# Power_-_3V3.net
KiCad netlist of a schematic drawn in Altium Designer
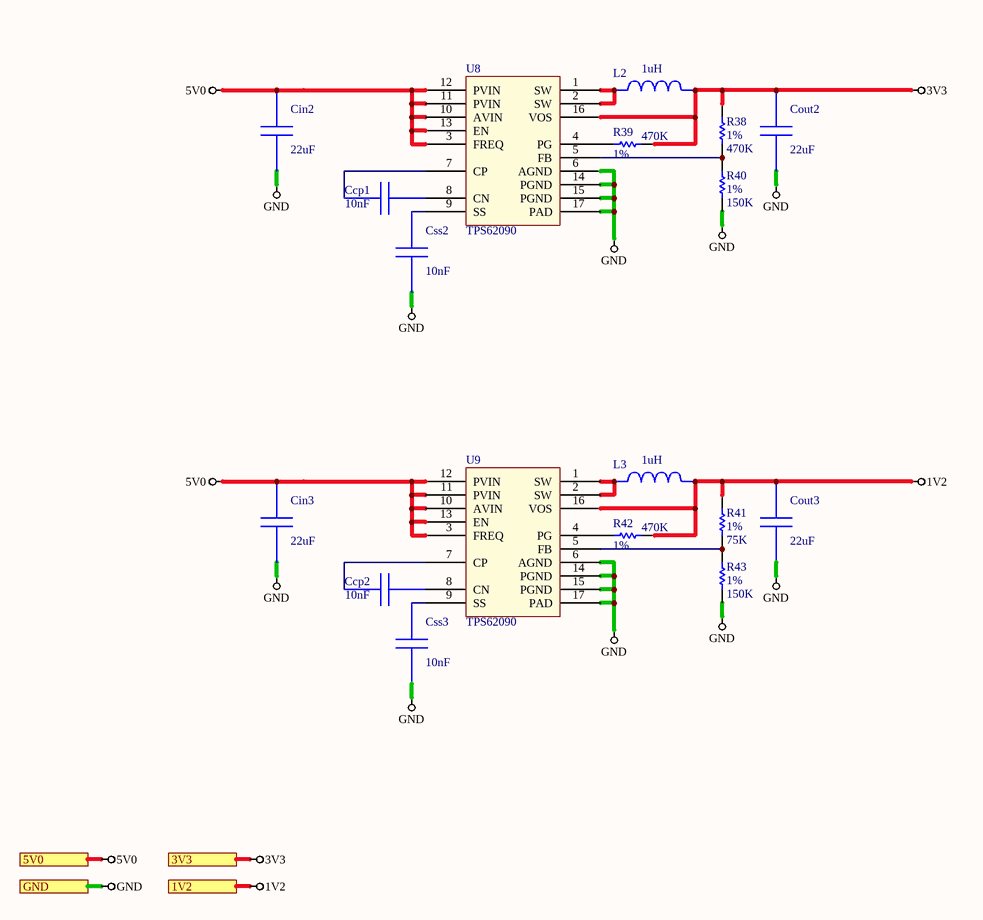
[diagram p0: Power - 3V3.SchDoc]

(export (version "E")
  (design (tool "Eeschema 10.0.6"))
  (components
    (comp (ref "Ccp1")
      (value "10nF")
      (footprint "CAPC0402(1005)60_L")
      (description "GRM155R71E103KA0")
      (fields (field (name "MANUFACTURER PART NUMBER") "GRM155R71E103KA01D"))
      (libsource (lib "TI WEBENCH") (part "Ccp"))
    )
    (comp (ref "Ccp2")
      (value "10nF")
      (footprint "CAPC0402(1005)60_L")
      (description "GRM155R71E103KA0")
      (fields (field (name "MANUFACTURER PART NUMBER") "GRM155R71E103KA01D"))
      (libsource (lib "TI WEBENCH") (part "Ccp"))
    )
    (comp (ref "Cin2")
      (value "22uF")
      (footprint "C-0805")
      (description "GRM21BR60J226ME3")
      (fields (field (name "MANUFACTURER PART NUMBER") "GRM21BR60J226ME39L"))
      (libsource (lib "TI WEBENCH") (part "Cout"))
    )
    (comp (ref "Cin3")
      (value "22uF")
      (footprint "C-0805")
      (description "GRM21BR60J226ME3")
      (fields (field (name "MANUFACTURER PART NUMBER") "GRM21BR60J226ME39L"))
      (libsource (lib "TI WEBENCH") (part "Cout"))
    )
    (comp (ref "Cout2")
      (value "22uF")
      (footprint "C-0805")
      (description "GRM21BR60J226ME3")
      (fields (field (name "MANUFACTURER PART NUMBER") "GRM21BR60J226ME39L"))
      (libsource (lib "TI WEBENCH") (part "Cout"))
    )
    (comp (ref "Cout3")
      (value "22uF")
      (footprint "C-0805")
      (description "GRM21BR60J226ME3")
      (fields (field (name "MANUFACTURER PART NUMBER") "GRM21BR60J226ME39L"))
      (libsource (lib "TI WEBENCH") (part "Cout"))
    )
    (comp (ref "Css2")
      (value "10nF")
      (footprint "CAPC0402(1005)60_L")
      (description "GRM155R71E103KA0")
      (fields (field (name "MANUFACTURER PART NUMBER") "GRM155R71E103KA01D"))
      (libsource (lib "TI WEBENCH") (part "Ccp"))
    )
    (comp (ref "Css3")
      (value "10nF")
      (footprint "CAPC0402(1005)60_L")
      (description "GRM155R71E103KA0")
      (fields (field (name "MANUFACTURER PART NUMBER") "GRM155R71E103KA01D"))
      (libsource (lib "TI WEBENCH") (part "Ccp"))
    )
    (comp (ref "L2")
      (value "1uH")
      (footprint "XFL4020")
      (fields (field (name "MANUFACTURER PART NUMBER") "XFL4020-102MEB"))
      (libsource (lib "FPGA-pcie") (part "Inductor-XFL4020-102MEB"))
    )
    (comp (ref "L3")
      (value "1uH")
      (footprint "XFL4020")
      (fields (field (name "MANUFACTURER PART NUMBER") "XFL4020-102MEB"))
      (libsource (lib "FPGA-pcie") (part "Inductor-XFL4020-102MEB"))
    )
    (comp (ref "R38")
      (value "1%")
      (footprint "RESC0402(1005)40_L")
      (description "Resistor")
      (fields (field (name "ALTIUM_VALUE") "470K") (field (name "PUBLISHER") "Altium Limited"))
      (libsource (lib "Miscellaneous Devices") (part "Res1"))
    )
    (comp (ref "R39")
      (value "1%")
      (footprint "RESC0402(1005)40_L")
      (description "Resistor")
      (fields (field (name "ALTIUM_VALUE") "470K") (field (name "PUBLISHER") "Altium Limited"))
      (libsource (lib "Miscellaneous Devices") (part "Res1"))
    )
    (comp (ref "R40")
      (value "1%")
      (footprint "RESC0402(1005)40_L")
      (description "Resistor")
      (fields (field (name "ALTIUM_VALUE") "150K") (field (name "PUBLISHER") "Altium Limited"))
      (libsource (lib "Miscellaneous Devices") (part "Res1"))
    )
    (comp (ref "R41")
      (value "1%")
      (footprint "RESC0402(1005)40_L")
      (description "Resistor")
      (fields (field (name "ALTIUM_VALUE") "75K") (field (name "PUBLISHER") "Altium Limited"))
      (libsource (lib "Miscellaneous Devices") (part "Res1"))
    )
    (comp (ref "R42")
      (value "1%")
      (footprint "RESC0402(1005)40_L")
      (description "Resistor")
      (fields (field (name "ALTIUM_VALUE") "470K") (field (name "PUBLISHER") "Altium Limited"))
      (libsource (lib "Miscellaneous Devices") (part "Res1"))
    )
    (comp (ref "R43")
      (value "1%")
      (footprint "RESC0402(1005)40_L")
      (description "Resistor")
      (fields (field (name "ALTIUM_VALUE") "150K") (field (name "PUBLISHER") "Altium Limited"))
      (libsource (lib "Miscellaneous Devices") (part "Res1"))
    )
    (comp (ref "U8")
      (value "TPS62090")
      (footprint "RGT16_1P7X1P7")
      (libsource (lib "Power") (part "TPS6209X"))
    )
    (comp (ref "U9")
      (value "TPS62090")
      (footprint "RGT16_1P7X1P7")
      (libsource (lib "Power") (part "TPS6209X"))
    )
  )
  (nets
    (net (code "1") (name "1V2") (class "Default")
      (node (ref "Cout3") (pin "1") (pinfunction "1_1") (pintype "passive"))
      (node (ref "L3") (pin "2") (pinfunction "2_2") (pintype "passive"))
      (node (ref "R41") (pin "2") (pinfunction "2_2") (pintype "passive"))
      (node (ref "R42") (pin "1") (pinfunction "1_1") (pintype "passive"))
      (node (ref "U9") (pin "16") (pinfunction "VOS_16") (pintype "passive"))
    )
    (net (code "2") (name "3V3") (class "Default")
      (node (ref "Cout2") (pin "1") (pinfunction "1_1") (pintype "passive"))
      (node (ref "L2") (pin "2") (pinfunction "2_2") (pintype "passive"))
      (node (ref "R38") (pin "2") (pinfunction "2_2") (pintype "passive"))
      (node (ref "R39") (pin "1") (pinfunction "1_1") (pintype "passive"))
      (node (ref "U8") (pin "16") (pinfunction "VOS_16") (pintype "passive"))
    )
    (net (code "3") (name "5V0") (class "Default")
      (node (ref "Cin2") (pin "1") (pinfunction "1_1") (pintype "passive"))
      (node (ref "Cin3") (pin "1") (pinfunction "1_1") (pintype "passive"))
      (node (ref "U8") (pin "10") (pinfunction "AVIN_10") (pintype "passive"))
      (node (ref "U8") (pin "11") (pinfunction "PVIN_11") (pintype "passive"))
      (node (ref "U8") (pin "12") (pinfunction "PVIN_12") (pintype "passive"))
      (node (ref "U8") (pin "13") (pinfunction "EN_13") (pintype "passive"))
      (node (ref "U8") (pin "3") (pinfunction "FREQ_3") (pintype "passive"))
      (node (ref "U9") (pin "10") (pinfunction "AVIN_10") (pintype "passive"))
      (node (ref "U9") (pin "11") (pinfunction "PVIN_11") (pintype "passive"))
      (node (ref "U9") (pin "12") (pinfunction "PVIN_12") (pintype "passive"))
      (node (ref "U9") (pin "13") (pinfunction "EN_13") (pintype "passive"))
      (node (ref "U9") (pin "3") (pinfunction "FREQ_3") (pintype "passive"))
    )
    (net (code "4") (name "GND") (class "Default")
      (node (ref "Cin2") (pin "2") (pinfunction "2_2") (pintype "passive"))
      (node (ref "Cin3") (pin "2") (pinfunction "2_2") (pintype "passive"))
      (node (ref "Cout2") (pin "2") (pinfunction "2_2") (pintype "passive"))
      (node (ref "Cout3") (pin "2") (pinfunction "2_2") (pintype "passive"))
      (node (ref "Css2") (pin "2") (pinfunction "2_2") (pintype "passive"))
      (node (ref "Css3") (pin "2") (pinfunction "2_2") (pintype "passive"))
      (node (ref "R40") (pin "1") (pinfunction "1_1") (pintype "passive"))
      (node (ref "R43") (pin "1") (pinfunction "1_1") (pintype "passive"))
      (node (ref "U8") (pin "14") (pinfunction "PGND_14") (pintype "passive"))
      (node (ref "U8") (pin "15") (pinfunction "PGND_15") (pintype "passive"))
      (node (ref "U8") (pin "17") (pinfunction "PAD_17") (pintype "passive"))
      (node (ref "U8") (pin "6") (pinfunction "AGND_6") (pintype "passive"))
      (node (ref "U9") (pin "14") (pinfunction "PGND_14") (pintype "passive"))
      (node (ref "U9") (pin "15") (pinfunction "PGND_15") (pintype "passive"))
      (node (ref "U9") (pin "17") (pinfunction "PAD_17") (pintype "passive"))
      (node (ref "U9") (pin "6") (pinfunction "AGND_6") (pintype "passive"))
    )
    (net (code "5") (name "Net-(L2-Pad1)") (class "Default")
      (node (ref "L2") (pin "1") (pinfunction "1_1") (pintype "passive"))
      (node (ref "U8") (pin "1") (pinfunction "SW_1") (pintype "passive"))
      (node (ref "U8") (pin "2") (pinfunction "SW_2") (pintype "passive"))
    )
    (net (code "6") (name "Net-(L3-Pad1)") (class "Default")
      (node (ref "L3") (pin "1") (pinfunction "1_1") (pintype "passive"))
      (node (ref "U9") (pin "1") (pinfunction "SW_1") (pintype "passive"))
      (node (ref "U9") (pin "2") (pinfunction "SW_2") (pintype "passive"))
    )
    (net (code "7") (name "Net-(U8-CN)") (class "Default")
      (node (ref "Ccp1") (pin "2") (pinfunction "2_2") (pintype "passive"))
      (node (ref "U8") (pin "8") (pinfunction "CN_8") (pintype "passive"))
    )
    (net (code "8") (name "Net-(U8-CP)") (class "Default")
      (node (ref "Ccp1") (pin "1") (pinfunction "1_1") (pintype "passive"))
      (node (ref "U8") (pin "7") (pinfunction "CP_7") (pintype "passive"))
    )
    (net (code "9") (name "Net-(U8-FB)") (class "Default")
      (node (ref "R38") (pin "1") (pinfunction "1_1") (pintype "passive"))
      (node (ref "R40") (pin "2") (pinfunction "2_2") (pintype "passive"))
      (node (ref "U8") (pin "5") (pinfunction "FB_5") (pintype "passive"))
    )
    (net (code "10") (name "Net-(U8-PG)") (class "Default")
      (node (ref "R39") (pin "2") (pinfunction "2_2") (pintype "passive"))
      (node (ref "U8") (pin "4") (pinfunction "PG_4") (pintype "passive"))
    )
    (net (code "11") (name "Net-(U8-SS)") (class "Default")
      (node (ref "Css2") (pin "1") (pinfunction "1_1") (pintype "passive"))
      (node (ref "U8") (pin "9") (pinfunction "SS_9") (pintype "passive"))
    )
    (net (code "12") (name "Net-(U9-CN)") (class "Default")
      (node (ref "Ccp2") (pin "2") (pinfunction "2_2") (pintype "passive"))
      (node (ref "U9") (pin "8") (pinfunction "CN_8") (pintype "passive"))
    )
    (net (code "13") (name "Net-(U9-CP)") (class "Default")
      (node (ref "Ccp2") (pin "1") (pinfunction "1_1") (pintype "passive"))
      (node (ref "U9") (pin "7") (pinfunction "CP_7") (pintype "passive"))
    )
    (net (code "14") (name "Net-(U9-FB)") (class "Default")
      (node (ref "R41") (pin "1") (pinfunction "1_1") (pintype "passive"))
      (node (ref "R43") (pin "2") (pinfunction "2_2") (pintype "passive"))
      (node (ref "U9") (pin "5") (pinfunction "FB_5") (pintype "passive"))
    )
    (net (code "15") (name "Net-(U9-PG)") (class "Default")
      (node (ref "R42") (pin "2") (pinfunction "2_2") (pintype "passive"))
      (node (ref "U9") (pin "4") (pinfunction "PG_4") (pintype "passive"))
    )
    (net (code "16") (name "Net-(U9-SS)") (class "Default")
      (node (ref "Css3") (pin "1") (pinfunction "1_1") (pintype "passive"))
      (node (ref "U9") (pin "9") (pinfunction "SS_9") (pintype "passive"))
    )
  )
)
